# FioSaber_Prototype_A.net
KiCad netlist of a schematic drawn in EAGLE
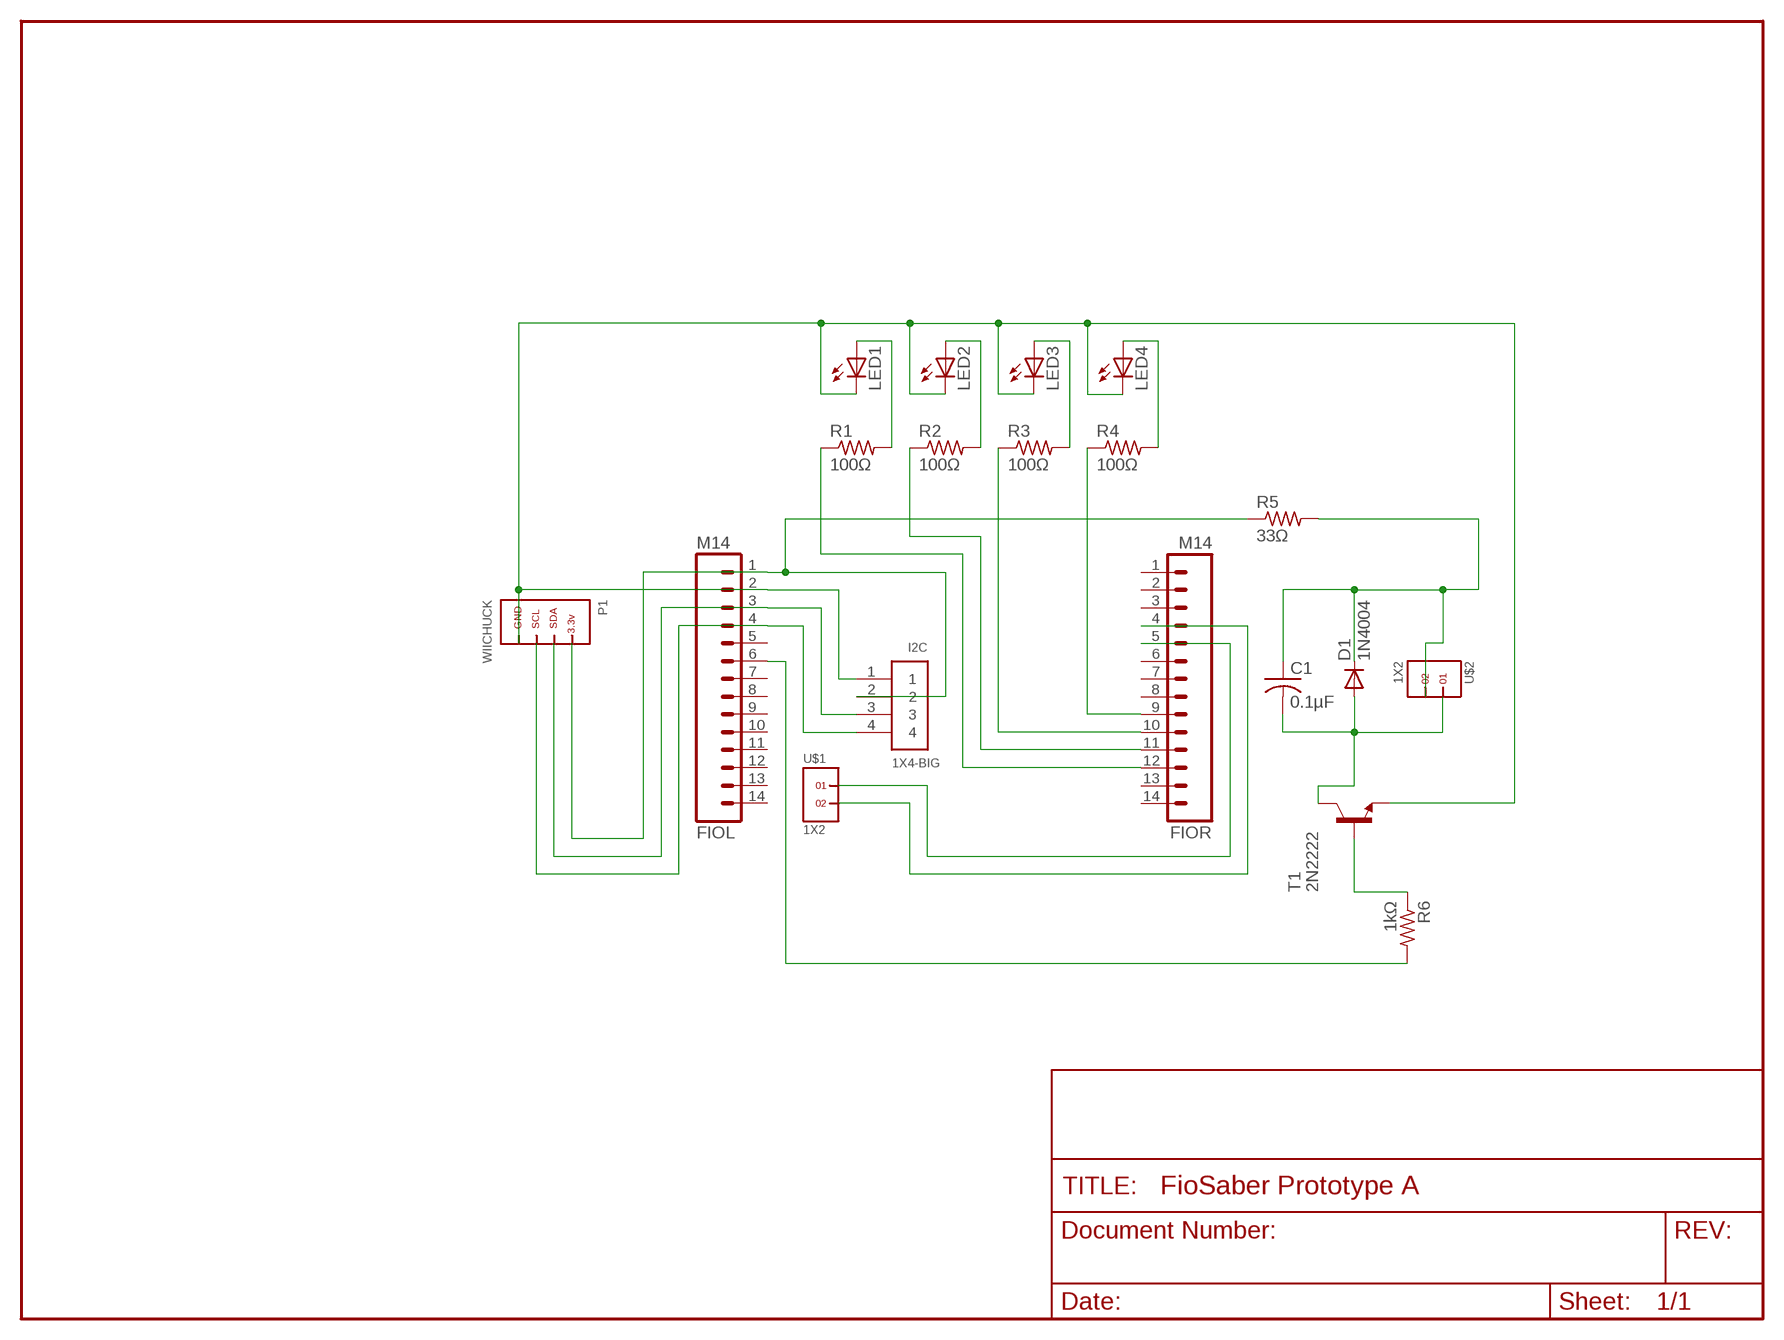
[diagram p0: schematic, sheet 1]

(export (version "E")
  (design (tool "Eeschema 10.0.6"))
  (components
    (comp (ref "C1")
      (value "0.1µF")
      (footprint "eagle-import:C025-025X050")
      (libsource (lib "eagle-import") (part "C-US025-025X050"))
    )
    (comp (ref "D1")
      (value "1N4004")
      (footprint "eagle-import:DO41-10")
      (libsource (lib "eagle-import") (part "1N4004"))
    )
    (comp (ref "FIOL")
      (value "M14")
      (footprint "eagle-import:1X14")
      (libsource (lib "eagle-import") (part "M14"))
    )
    (comp (ref "FIOR")
      (value "M14")
      (footprint "eagle-import:1X14")
      (libsource (lib "eagle-import") (part "M14"))
    )
    (comp (ref "I2C")
      (value "1X4-BIG")
      (footprint "eagle-import:1X04-BIG")
      (libsource (lib "eagle-import") (part "1X4-BIG"))
    )
    (comp (ref "LED1")
      (value "LED3MM")
      (footprint "eagle-import:LED3MM")
      (libsource (lib "eagle-import") (part "LED3MM"))
    )
    (comp (ref "LED2")
      (value "LED3MM")
      (footprint "eagle-import:LED3MM")
      (libsource (lib "eagle-import") (part "LED3MM"))
    )
    (comp (ref "LED3")
      (value "LED3MM")
      (footprint "eagle-import:LED3MM")
      (libsource (lib "eagle-import") (part "LED3MM"))
    )
    (comp (ref "LED4")
      (value "LED3MM")
      (footprint "eagle-import:LED3MM")
      (libsource (lib "eagle-import") (part "LED3MM"))
    )
    (comp (ref "P1")
      (value "WIICHUCK")
      (footprint "eagle-import:MEMOREX_RECEIVER")
      (libsource (lib "eagle-import") (part "WIICHUCK"))
    )
    (comp (ref "R1")
      (value "100Ω")
      (footprint "eagle-import:0207_10")
      (libsource (lib "eagle-import") (part "R-US_0207/10"))
    )
    (comp (ref "R2")
      (value "100Ω")
      (footprint "eagle-import:0207_10")
      (libsource (lib "eagle-import") (part "R-US_0207/10"))
    )
    (comp (ref "R3")
      (value "100Ω")
      (footprint "eagle-import:0207_10")
      (libsource (lib "eagle-import") (part "R-US_0207/10"))
    )
    (comp (ref "R4")
      (value "100Ω")
      (footprint "eagle-import:0207_10")
      (libsource (lib "eagle-import") (part "R-US_0207/10"))
    )
    (comp (ref "R5")
      (value "33Ω")
      (footprint "eagle-import:0207_10")
      (libsource (lib "eagle-import") (part "R-US_0207/10"))
    )
    (comp (ref "R6")
      (value "1kΩ")
      (footprint "eagle-import:0207_10")
      (libsource (lib "eagle-import") (part "R-US_0207/10"))
    )
    (comp (ref "T1")
      (value "2N2222")
      (footprint "eagle-import:TO92-EBC-OVAL")
      (libsource (lib "eagle-import") (part "2N2222"))
    )
    (comp (ref "U$1")
      (value "1X2")
      (footprint "eagle-import:1X2")
      (libsource (lib "eagle-import") (part "1X2"))
    )
    (comp (ref "U$2")
      (value "1X2")
      (footprint "eagle-import:1X2")
      (libsource (lib "eagle-import") (part "1X2"))
    )
  )
  (nets
    (net (code "1") (name "Net-(C1-Pad1)") (class "Default")
      (node (ref "C1") (pin "1") (pinfunction "1_1") (pintype "passive"))
      (node (ref "D1") (pin "C") (pinfunction "C_C") (pintype "passive"))
      (node (ref "R5") (pin "2") (pinfunction "2_2") (pintype "passive"))
      (node (ref "U$2") (pin "2") (pinfunction "2_2") (pintype "bidirectional"))
    )
    (net (code "2") (name "Net-(C1-Pad2)") (class "Default")
      (node (ref "C1") (pin "2") (pinfunction "2_2") (pintype "passive"))
      (node (ref "D1") (pin "A") (pinfunction "A_A") (pintype "passive"))
      (node (ref "T1") (pin "C") (pinfunction "C_C") (pintype "passive"))
      (node (ref "U$2") (pin "1") (pinfunction "1_1") (pintype "bidirectional"))
    )
    (net (code "3") (name "Net-(FIOL-Pad1)") (class "Default")
      (node (ref "FIOL") (pin "1") (pinfunction "1_1") (pintype "passive"))
      (node (ref "I2C") (pin "2") (pinfunction "2_2") (pintype "bidirectional"))
      (node (ref "P1") (pin "PWR") (pinfunction "PWR_PWR") (pintype "bidirectional"))
      (node (ref "R5") (pin "1") (pinfunction "1_1") (pintype "passive"))
    )
    (net (code "4") (name "Net-(FIOL-Pad3)") (class "Default")
      (node (ref "FIOL") (pin "3") (pinfunction "3_3") (pintype "passive"))
      (node (ref "I2C") (pin "3") (pinfunction "3_3") (pintype "bidirectional"))
      (node (ref "P1") (pin "SDA") (pinfunction "SDA_SDA") (pintype "bidirectional"))
    )
    (net (code "5") (name "Net-(FIOL-Pad4)") (class "Default")
      (node (ref "FIOL") (pin "4") (pinfunction "4_4") (pintype "passive"))
      (node (ref "I2C") (pin "4") (pinfunction "4_4") (pintype "bidirectional"))
      (node (ref "P1") (pin "SCL") (pinfunction "SCL_SCL") (pintype "bidirectional"))
    )
    (net (code "6") (name "Net-(FIOL-Pad6)") (class "Default")
      (node (ref "FIOL") (pin "6") (pinfunction "6_6") (pintype "passive"))
      (node (ref "R6") (pin "2") (pinfunction "2_2") (pintype "passive"))
    )
    (net (code "7") (name "Net-(FIOR-Pad4)") (class "Default")
      (node (ref "FIOR") (pin "4") (pinfunction "4_4") (pintype "passive"))
      (node (ref "U$1") (pin "2") (pinfunction "2_2") (pintype "bidirectional"))
    )
    (net (code "8") (name "Net-(FIOR-Pad5)") (class "Default")
      (node (ref "FIOR") (pin "5") (pinfunction "5_5") (pintype "passive"))
      (node (ref "U$1") (pin "1") (pinfunction "1_1") (pintype "bidirectional"))
    )
    (net (code "9") (name "Net-(FIOR-Pad9)") (class "Default")
      (node (ref "FIOR") (pin "9") (pinfunction "9_9") (pintype "passive"))
      (node (ref "R4") (pin "1") (pinfunction "1_1") (pintype "passive"))
    )
    (net (code "10") (name "Net-(FIOR-Pad10)") (class "Default")
      (node (ref "FIOR") (pin "10") (pinfunction "10_10") (pintype "passive"))
      (node (ref "R3") (pin "1") (pinfunction "1_1") (pintype "passive"))
    )
    (net (code "11") (name "Net-(FIOR-Pad11)") (class "Default")
      (node (ref "FIOR") (pin "11") (pinfunction "11_11") (pintype "passive"))
      (node (ref "R2") (pin "1") (pinfunction "1_1") (pintype "passive"))
    )
    (net (code "12") (name "Net-(FIOR-Pad12)") (class "Default")
      (node (ref "FIOR") (pin "12") (pinfunction "12_12") (pintype "passive"))
      (node (ref "R1") (pin "1") (pinfunction "1_1") (pintype "passive"))
    )
    (net (code "13") (name "Net-(LED1-C)") (class "Default")
      (node (ref "FIOL") (pin "2") (pinfunction "2_2") (pintype "passive"))
      (node (ref "I2C") (pin "1") (pinfunction "1_1") (pintype "bidirectional"))
      (node (ref "LED1") (pin "K") (pinfunction "C_K") (pintype "passive"))
      (node (ref "LED2") (pin "K") (pinfunction "C_K") (pintype "passive"))
      (node (ref "LED3") (pin "K") (pinfunction "C_K") (pintype "passive"))
      (node (ref "LED4") (pin "K") (pinfunction "C_K") (pintype "passive"))
      (node (ref "P1") (pin "GND") (pinfunction "GND_GND") (pintype "bidirectional"))
      (node (ref "T1") (pin "E") (pinfunction "E_E") (pintype "passive"))
    )
    (net (code "14") (name "Net-(LED1-PadA)") (class "Default")
      (node (ref "LED1") (pin "A") (pinfunction "A_A") (pintype "passive"))
      (node (ref "R1") (pin "2") (pinfunction "2_2") (pintype "passive"))
    )
    (net (code "15") (name "Net-(LED2-PadA)") (class "Default")
      (node (ref "LED2") (pin "A") (pinfunction "A_A") (pintype "passive"))
      (node (ref "R2") (pin "2") (pinfunction "2_2") (pintype "passive"))
    )
    (net (code "16") (name "Net-(LED3-PadA)") (class "Default")
      (node (ref "LED3") (pin "A") (pinfunction "A_A") (pintype "passive"))
      (node (ref "R3") (pin "2") (pinfunction "2_2") (pintype "passive"))
    )
    (net (code "17") (name "Net-(LED4-PadA)") (class "Default")
      (node (ref "LED4") (pin "A") (pinfunction "A_A") (pintype "passive"))
      (node (ref "R4") (pin "2") (pinfunction "2_2") (pintype "passive"))
    )
    (net (code "18") (name "Net-(R6-Pad1)") (class "Default")
      (node (ref "R6") (pin "1") (pinfunction "1_1") (pintype "passive"))
      (node (ref "T1") (pin "B") (pinfunction "B_B") (pintype "passive"))
    )
    (net (code "19") (name "unconnected-(FIOL-Pad5)") (class "Default")
      (node (ref "FIOL") (pin "5") (pinfunction "5_5") (pintype "passive"))
    )
    (net (code "20") (name "unconnected-(FIOL-Pad7)") (class "Default")
      (node (ref "FIOL") (pin "7") (pinfunction "7_7") (pintype "passive"))
    )
    (net (code "21") (name "unconnected-(FIOL-Pad8)") (class "Default")
      (node (ref "FIOL") (pin "8") (pinfunction "8_8") (pintype "passive"))
    )
    (net (code "22") (name "unconnected-(FIOL-Pad9)") (class "Default")
      (node (ref "FIOL") (pin "9") (pinfunction "9_9") (pintype "passive"))
    )
    (net (code "23") (name "unconnected-(FIOL-Pad10)") (class "Default")
      (node (ref "FIOL") (pin "10") (pinfunction "10_10") (pintype "passive"))
    )
    (net (code "24") (name "unconnected-(FIOL-Pad11)") (class "Default")
      (node (ref "FIOL") (pin "11") (pinfunction "11_11") (pintype "passive"))
    )
    (net (code "25") (name "unconnected-(FIOL-Pad12)") (class "Default")
      (node (ref "FIOL") (pin "12") (pinfunction "12_12") (pintype "passive"))
    )
    (net (code "26") (name "unconnected-(FIOL-Pad13)") (class "Default")
      (node (ref "FIOL") (pin "13") (pinfunction "13_13") (pintype "passive"))
    )
    (net (code "27") (name "unconnected-(FIOL-Pad14)") (class "Default")
      (node (ref "FIOL") (pin "14") (pinfunction "14_14") (pintype "passive"))
    )
    (net (code "28") (name "unconnected-(FIOR-Pad1)") (class "Default")
      (node (ref "FIOR") (pin "1") (pinfunction "1_1") (pintype "passive"))
    )
    (net (code "29") (name "unconnected-(FIOR-Pad2)") (class "Default")
      (node (ref "FIOR") (pin "2") (pinfunction "2_2") (pintype "passive"))
    )
    (net (code "30") (name "unconnected-(FIOR-Pad3)") (class "Default")
      (node (ref "FIOR") (pin "3") (pinfunction "3_3") (pintype "passive"))
    )
    (net (code "31") (name "unconnected-(FIOR-Pad6)") (class "Default")
      (node (ref "FIOR") (pin "6") (pinfunction "6_6") (pintype "passive"))
    )
    (net (code "32") (name "unconnected-(FIOR-Pad7)") (class "Default")
      (node (ref "FIOR") (pin "7") (pinfunction "7_7") (pintype "passive"))
    )
    (net (code "33") (name "unconnected-(FIOR-Pad8)") (class "Default")
      (node (ref "FIOR") (pin "8") (pinfunction "8_8") (pintype "passive"))
    )
    (net (code "34") (name "unconnected-(FIOR-Pad13)") (class "Default")
      (node (ref "FIOR") (pin "13") (pinfunction "13_13") (pintype "passive"))
    )
    (net (code "35") (name "unconnected-(FIOR-Pad14)") (class "Default")
      (node (ref "FIOR") (pin "14") (pinfunction "14_14") (pintype "passive"))
    )
  )
)
